# BMS_Design_3_New_Part_Monitor.net
KiCad netlist of a schematic drawn in Altium Designer
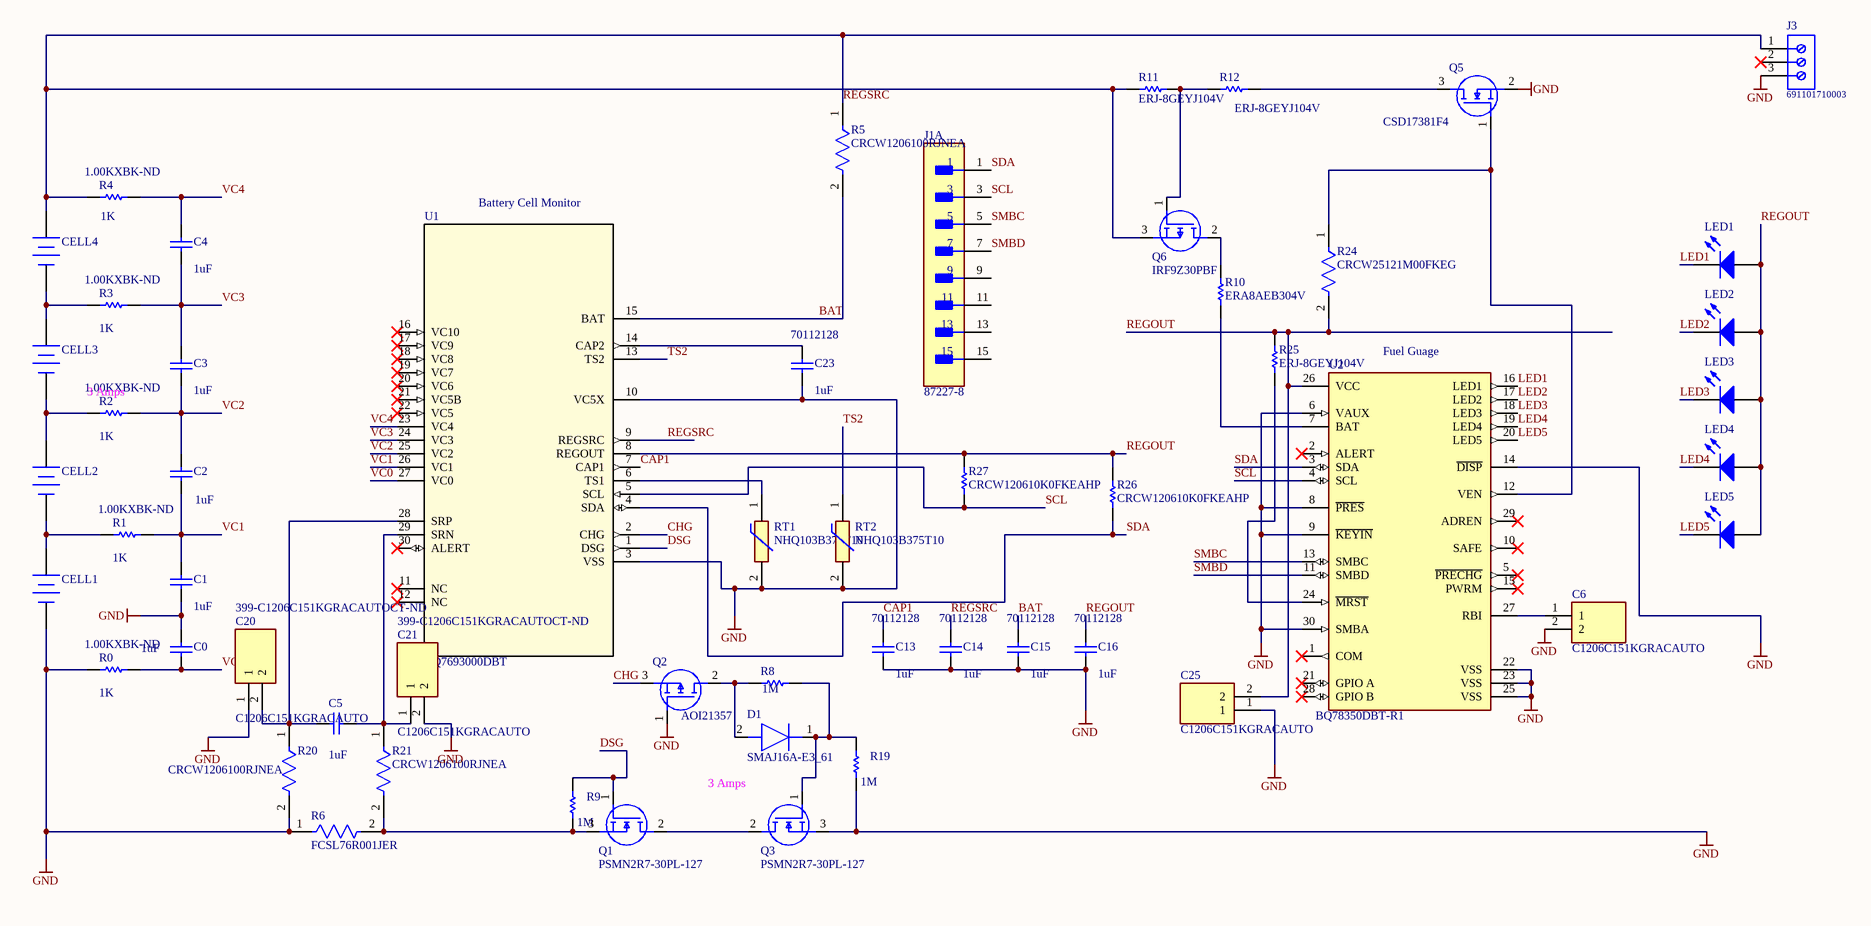
[diagram p0: BMS Design 3 New Part Monitor.SchDoc]

(export (version "E")
  (design (tool "Eeschema 10.0.6"))
  (components
    (comp (ref "C0")
      (value "1uF")
      (footprint "RAD-0.3")
      (description "Capacitor")
      (fields (field (name "PUBLISHER") "Altium Limited"))
      (libsource (lib "Miscellaneous Devices") (part "Cap"))
    )
    (comp (ref "C1")
      (value "1uF")
      (footprint "RAD-0.3")
      (description "Capacitor")
      (fields (field (name "PUBLISHER") "Altium Limited"))
      (libsource (lib "Miscellaneous Devices") (part "Cap"))
    )
    (comp (ref "C2")
      (value "1uF")
      (footprint "RAD-0.3")
      (description "Capacitor")
      (fields (field (name "PUBLISHER") "Altium Limited"))
      (libsource (lib "Miscellaneous Devices") (part "Cap"))
    )
    (comp (ref "C3")
      (value "1uF")
      (footprint "RAD-0.3")
      (description "Capacitor")
      (fields (field (name "PUBLISHER") "Altium Limited"))
      (libsource (lib "Miscellaneous Devices") (part "Cap"))
    )
    (comp (ref "C4")
      (value "1uF")
      (footprint "RAD-0.3")
      (description "Capacitor")
      (fields (field (name "PUBLISHER") "Altium Limited"))
      (libsource (lib "Miscellaneous Devices") (part "Cap"))
    )
    (comp (ref "C5")
      (value "1uF")
      (footprint "RAD-0.3")
      (description "Capacitor")
      (fields (field (name "PUBLISHER") "Altium Limited"))
      (libsource (lib "Miscellaneous Devices") (part "Cap"))
    )
    (comp (ref "C6")
      (value "C1206C151KGRACAUTO")
      (footprint "SamacSys:CAPC3216X180N")
      (description "Capacitor Network")
      (libsource (lib "*") (part "C1206C151KGRACAUTO"))
    )
    (comp (ref "C13")
      (value "1uF")
      (footprint "RAD-0.3")
      (description "Capacitor")
      (fields (field (name "SUPPLIER PART NUMBER 1") "70112128") (field (name "PUBLISHER") "Altium Limited"))
      (libsource (lib "Miscellaneous Devices") (part "Cap"))
    )
    (comp (ref "C14")
      (value "1uF")
      (footprint "RAD-0.3")
      (description "Capacitor")
      (fields (field (name "SUPPLIER PART NUMBER 1") "70112128") (field (name "PUBLISHER") "Altium Limited"))
      (libsource (lib "Miscellaneous Devices") (part "Cap"))
    )
    (comp (ref "C15")
      (value "1uF")
      (footprint "RAD-0.3")
      (description "Capacitor")
      (fields (field (name "SUPPLIER PART NUMBER 1") "70112128") (field (name "PUBLISHER") "Altium Limited"))
      (libsource (lib "Miscellaneous Devices") (part "Cap"))
    )
    (comp (ref "C16")
      (value "1uF")
      (footprint "RAD-0.3")
      (description "Capacitor")
      (fields (field (name "SUPPLIER PART NUMBER 1") "70112128") (field (name "PUBLISHER") "Altium Limited"))
      (libsource (lib "Miscellaneous Devices") (part "Cap"))
    )
    (comp (ref "C20")
      (value "C1206C151KGRACAUTO")
      (footprint "SamacSys:CAPC3216X180N")
      (description "Capacitor Network")
      (fields (field (name "SUPPLIER PART NUMBER 1") "399-C1206C151KGRACAUTOCT-ND"))
      (libsource (lib "") (part "C1206C151KGRACAUTO_1"))
    )
    (comp (ref "C21")
      (value "C1206C151KGRACAUTO")
      (footprint "SamacSys:CAPC3216X180N")
      (description "Capacitor Network")
      (fields (field (name "SUPPLIER PART NUMBER 1") "399-C1206C151KGRACAUTOCT-ND"))
      (libsource (lib "") (part "C1206C151KGRACAUTO_1"))
    )
    (comp (ref "C23")
      (value "1uF")
      (footprint "RAD-0.3")
      (description "Capacitor")
      (fields (field (name "SUPPLIER PART NUMBER 1") "70112128") (field (name "PUBLISHER") "Altium Limited"))
      (libsource (lib "Miscellaneous Devices") (part "Cap"))
    )
    (comp (ref "C25")
      (value "C1206C151KGRACAUTO")
      (footprint "SamacSys:CAPC3216X180N")
      (description "Capacitor Network")
      (libsource (lib "") (part "C1206C151KGRACAUTO_2"))
    )
    (comp (ref "CELL1")
      (value "~")
      (footprint "BAT-2")
      (description "Multicell Battery")
      (fields (field (name "PUBLISHER") "Altium Limited"))
      (libsource (lib "Miscellaneous Devices") (part "Battery"))
    )
    (comp (ref "CELL2")
      (value "~")
      (footprint "BAT-2")
      (description "Multicell Battery")
      (fields (field (name "PUBLISHER") "Altium Limited"))
      (libsource (lib "Miscellaneous Devices") (part "Battery"))
    )
    (comp (ref "CELL3")
      (value "~")
      (footprint "BAT-2")
      (description "Multicell Battery")
      (fields (field (name "PUBLISHER") "Altium Limited"))
      (libsource (lib "Miscellaneous Devices") (part "Battery"))
    )
    (comp (ref "CELL4")
      (value "~")
      (footprint "BAT-2")
      (description "Multicell Battery")
      (fields (field (name "PUBLISHER") "Altium Limited"))
      (libsource (lib "Miscellaneous Devices") (part "Battery"))
    )
    (comp (ref "D1")
      (value "SMAJ16A-E3_61")
      (footprint "SamacSys:DIOM5127X229N")
      (description "Diode")
      (fields
        (field (name "MANUFACTURER_PART_NUMBER") "SMAJ16A-E3/61")
        (field (name "MOUSER PART NUMBER") "625-SMAJ16A-E3")
      )
      (libsource (lib "*") (part "SMAJ16A-E3_61"))
    )
    (comp (ref "J1")
      (value "87227-8")
      (footprint "FP-87227-8-MFG")
      (description "CONN HEADER VERT 16POS 2.54MM")
      (fields
        (field (name "MANUFACTURER") "TE Connectivity")
        (field (name "OCTOPART") "https://octopart.com/87227-8-te+connectivity-39407754")
      )
      (libsource (lib "Altium Content Vault") (part "4b6d22b45e2f925f038cba5d936fbcc"))
    )
    (comp (ref "J3")
      (value "691101710003")
      (footprint "691101710003")
      (description "Series 101 - 5.00 mm Horizontal Entry Modular with Pressure Clamp WR-TBL, 3 pin")
      (fields (field (name "MANUFACTURER") "Wurth Elektronik") (field (name "PUBLISHER") "WurthElektronik"))
      (libsource (lib "Altium Content Vault") (part "WE-CN-1P-F-TB3"))
    )
    (comp (ref "LED1")
      (value "~")
      (footprint "LED-0")
      (description "Typical INFRARED GaAs LED")
      (fields (field (name "PUBLISHER") "Altium Limited"))
      (libsource (lib "Miscellaneous Devices") (part "LED0"))
    )
    (comp (ref "LED2")
      (value "~")
      (footprint "LED-0")
      (description "Typical INFRARED GaAs LED")
      (fields (field (name "PUBLISHER") "Altium Limited"))
      (libsource (lib "Miscellaneous Devices") (part "LED0"))
    )
    (comp (ref "LED3")
      (value "~")
      (footprint "LED-0")
      (description "Typical INFRARED GaAs LED")
      (fields (field (name "PUBLISHER") "Altium Limited"))
      (libsource (lib "Miscellaneous Devices") (part "LED0"))
    )
    (comp (ref "LED4")
      (value "~")
      (footprint "LED-0")
      (description "Typical INFRARED GaAs LED")
      (fields (field (name "PUBLISHER") "Altium Limited"))
      (libsource (lib "Miscellaneous Devices") (part "LED0"))
    )
    (comp (ref "LED5")
      (value "~")
      (footprint "LED-0")
      (description "Typical INFRARED GaAs LED")
      (fields (field (name "PUBLISHER") "Altium Limited"))
      (libsource (lib "Miscellaneous Devices") (part "LED0"))
    )
    (comp (ref "Q1")
      (value "PSMN2R7-30PL-127")
      (footprint "TO-220AB")
      (description "MOSFET (N-Channel)")
      (fields
        (field (name "MANUFACTURER_PART_NUMBER") "PSMN2R7-30PL,127")
        (field (name "MOUSER PART NUMBER") "771-PSMN2R730PL127")
      )
      (libsource (lib "*") (part "PSMN2R7-30PL,127"))
    )
    (comp (ref "Q2")
      (value "AOI21357")
      (footprint "SamacSys:TO229P239X654X854-3P")
      (description "MOSFET (P-Channel)")
      (libsource (lib "*") (part "AOI21357"))
    )
    (comp (ref "Q3")
      (value "PSMN2R7-30PL-127")
      (footprint "TO-220AB")
      (description "MOSFET (N-Channel)")
      (fields
        (field (name "MANUFACTURER_PART_NUMBER") "PSMN2R7-30PL,127")
        (field (name "MOUSER PART NUMBER") "771-PSMN2R730PL127")
      )
      (libsource (lib "*") (part "PSMN2R7-30PL,127"))
    )
    (comp (ref "Q5")
      (value "CSD17381F4")
      (footprint "SamacSys:CSD17381F4")
      (description "MOSFET (N-Channel)")
      (libsource (lib "*") (part "CSD17381F4"))
    )
    (comp (ref "Q6")
      (value "IRF9Z30PBF")
      (footprint "SamacSys:TO254P465X1024X2050-3P")
      (description "MOSFET (P-Channel)")
      (fields (field (name "MOUSER PART NUMBER") "844-IRF9Z30PBF"))
      (libsource (lib "*") (part "IRF9Z30PBF"))
    )
    (comp (ref "R0")
      (value "1K")
      (footprint "AXIAL-0.3")
      (description "Resistor")
      (fields
        (field (name "SUPPLIER PART NUMBER 1") "1.00KXBK-ND")
        (field (name "PUBLISHER") "Altium Limited")
      )
      (libsource (lib "Miscellaneous Devices") (part "Res1"))
    )
    (comp (ref "R1")
      (value "1K")
      (footprint "AXIAL-0.3")
      (description "Resistor")
      (fields
        (field (name "SUPPLIER PART NUMBER 1") "1.00KXBK-ND")
        (field (name "PUBLISHER") "Altium Limited")
      )
      (libsource (lib "Miscellaneous Devices") (part "Res1"))
    )
    (comp (ref "R2")
      (value "1K")
      (footprint "AXIAL-0.3")
      (description "Resistor")
      (fields
        (field (name "SUPPLIER PART NUMBER 1") "1.00KXBK-ND")
        (field (name "PUBLISHER") "Altium Limited")
      )
      (libsource (lib "Miscellaneous Devices") (part "Res1"))
    )
    (comp (ref "R3")
      (value "1K")
      (footprint "AXIAL-0.3")
      (description "Resistor")
      (fields
        (field (name "SUPPLIER PART NUMBER 1") "1.00KXBK-ND")
        (field (name "PUBLISHER") "Altium Limited")
      )
      (libsource (lib "Miscellaneous Devices") (part "Res1"))
    )
    (comp (ref "R4")
      (value "1K")
      (footprint "AXIAL-0.3")
      (description "Resistor")
      (fields
        (field (name "SUPPLIER PART NUMBER 1") "1.00KXBK-ND")
        (field (name "PUBLISHER") "Altium Limited")
      )
      (libsource (lib "Miscellaneous Devices") (part "Res1"))
    )
    (comp (ref "R5")
      (value "CRCW1206100RJNEA")
      (footprint "FP-CRCW1206-e3-IPC_B")
      (description "RES Thick Film, 100Ω, 5%, 0.25W, 200ppm/°C, 1206")
      (fields (field (name "TOLERANCE") "5%"))
      (libsource (lib "Altium Content Vault") (part "1029c3af85768c4190bb7ad29bc67b5"))
    )
    (comp (ref "R6")
      (value "FCSL76R001JER")
      (footprint "FP-FCSL76-0R001-MFG")
      (description "RES 0.001 OHM 3W 3015 WIDE")
      (fields (field (name "TOLERANCE") "5%"))
      (libsource (lib "Altium Content Vault") (part "1029c3af85768c4190bb7ad29bc67b5"))
    )
    (comp (ref "R8")
      (value "1M")
      (footprint "AXIAL-0.3")
      (description "Resistor")
      (fields (field (name "PUBLISHER") "Altium Limited"))
      (libsource (lib "Miscellaneous Devices") (part "Res1"))
    )
    (comp (ref "R9")
      (value "1M")
      (footprint "AXIAL-0.3")
      (description "Resistor")
      (fields (field (name "PUBLISHER") "Altium Limited"))
      (libsource (lib "Miscellaneous Devices") (part "Res1"))
    )
    (comp (ref "R10")
      (value "ERA8AEB304V")
      (footprint "RESC3216X70X50LL20T25")
      (fields (field (name "MANUFACTURER") "Panasonic"))
      (libsource (lib "Altium Content Vault") (part "RES"))
    )
    (comp (ref "R11")
      (value "ERJ-8GEYJ104V")
      (footprint "RESC3216X70X50LL05T20")
      (fields (field (name "MANUFACTURER") "Panasonic"))
      (libsource (lib "Altium Content Vault") (part "RES"))
    )
    (comp (ref "R12")
      (value "ERJ-8GEYJ104V")
      (footprint "RESC3216X70X50LL05T20")
      (fields (field (name "MANUFACTURER") "Panasonic"))
      (libsource (lib "Altium Content Vault") (part "RES"))
    )
    (comp (ref "R19")
      (value "1M")
      (footprint "AXIAL-0.3")
      (description "Resistor")
      (fields (field (name "PUBLISHER") "Altium Limited"))
      (libsource (lib "Miscellaneous Devices") (part "Res1"))
    )
    (comp (ref "R20")
      (value "CRCW1206100RJNEA")
      (footprint "FP-CRCW1206-e3-IPC_B")
      (description "RES Thick Film, 100Ω, 5%, 0.25W, 200ppm/°C, 1206")
      (fields (field (name "TOLERANCE") "5%"))
      (libsource (lib "Altium Content Vault") (part "1029c3af85768c4190bb7ad29bc67b5"))
    )
    (comp (ref "R21")
      (value "CRCW1206100RJNEA")
      (footprint "FP-CRCW1206-e3-IPC_B")
      (description "RES Thick Film, 100Ω, 5%, 0.25W, 200ppm/°C, 1206")
      (fields (field (name "TOLERANCE") "5%"))
      (libsource (lib "Altium Content Vault") (part "1029c3af85768c4190bb7ad29bc67b5"))
    )
    (comp (ref "R24")
      (value "CRCW25121M00FKEG")
      (footprint "FP-CRCW2512-e3-IPC_C")
      (description "RES Thick Film, 1MΩ, 1%, 1W, 100ppm/°C, 2512")
      (fields (field (name "TOLERANCE") "1%"))
      (libsource (lib "Altium Content Vault") (part "1029c3af85768c4190bb7ad29bc67b5"))
    )
    (comp (ref "R25")
      (value "ERJ-8GEYJ104V")
      (footprint "RESC3216X70X50LL05T20")
      (fields (field (name "MANUFACTURER") "Panasonic"))
      (libsource (lib "Altium Content Vault") (part "RES"))
    )
    (comp (ref "R26")
      (value "CRCW120610K0FKEAHP")
      (footprint "RESC3116X65X50NL20T20")
      (fields (field (name "MANUFACTURER") "Vishay Dale"))
      (libsource (lib "Altium Content Vault") (part "RES"))
    )
    (comp (ref "R27")
      (value "CRCW120610K0FKEAHP")
      (footprint "RESC3116X65X50NL20T20")
      (fields (field (name "MANUFACTURER") "Vishay Dale"))
      (libsource (lib "Altium Content Vault") (part "RES"))
    )
    (comp (ref "RT1")
      (value "NHQ103B375T10")
      (footprint "SamacSys:RESC2113X66N")
      (description "Thermistor")
      (libsource (lib "*") (part "NHQ103B375T10"))
    )
    (comp (ref "RT2")
      (value "NHQ103B375T10")
      (footprint "SamacSys:RESC2113X66N")
      (description "Thermistor")
      (libsource (lib "*") (part "NHQ103B375T10"))
    )
    (comp (ref "U1")
      (value "BQ7693000DBT")
      (footprint "BQ7693000DBT:DBT0030A_N")
      (description "No Description Available")
      (fields (field (name "COPYRIGHT") "Copyright (C) 2022 Ultra Librarian. All rights reserved."))
      (libsource (lib "BQ7693000DBT") (part "BQ7693000DBT"))
    )
    (comp (ref "U2")
      (value "BQ78350DBT-R1")
      (footprint "FP-DBT0030A-IPC_C")
      (description "IC BATTERY MGMT CTRLR 30TSSOP")
      (libsource (lib "Altium Content Vault") (part "ce2f43281ae33b5194046e95201acc2"))
    )
  )
  (nets
    (net (code "1") (name "/BAT") (class "Default")
      (node (ref "C15") (pin "2") (pinfunction "2_2") (pintype "passive"))
      (node (ref "R5") (pin "2") (pinfunction "2_2") (pintype "passive"))
      (node (ref "U1") (pin "15") (pinfunction "BAT_15") (pintype "power_in"))
    )
    (net (code "2") (name "/CAP1") (class "Default")
      (node (ref "C13") (pin "2") (pinfunction "2_2") (pintype "passive"))
      (node (ref "U1") (pin "7") (pinfunction "CAP1_7") (pintype "output"))
    )
    (net (code "3") (name "/CHG") (class "Default")
      (node (ref "Q2") (pin "3") (pinfunction "S_3") (pintype "passive"))
      (node (ref "U1") (pin "2") (pinfunction "CHG_2") (pintype "output"))
    )
    (net (code "4") (name "/DSG") (class "Default")
      (node (ref "Q1") (pin "1") (pinfunction "G_1") (pintype "passive"))
      (node (ref "R9") (pin "2") (pinfunction "2_2") (pintype "passive"))
      (node (ref "U1") (pin "1") (pinfunction "DSG_1") (pintype "output"))
    )
    (net (code "5") (name "/LED1") (class "Default")
      (node (ref "LED1") (pin "2") (pinfunction "K_2") (pintype "passive"))
      (node (ref "U2") (pin "16") (pinfunction "LED1_16") (pintype "output"))
    )
    (net (code "6") (name "/LED2") (class "Default")
      (node (ref "LED2") (pin "2") (pinfunction "K_2") (pintype "passive"))
      (node (ref "U2") (pin "17") (pinfunction "LED2_17") (pintype "output"))
    )
    (net (code "7") (name "/LED3") (class "Default")
      (node (ref "LED3") (pin "2") (pinfunction "K_2") (pintype "passive"))
      (node (ref "U2") (pin "18") (pinfunction "LED3_18") (pintype "output"))
    )
    (net (code "8") (name "/LED4") (class "Default")
      (node (ref "LED4") (pin "2") (pinfunction "K_2") (pintype "passive"))
      (node (ref "U2") (pin "19") (pinfunction "LED4_19") (pintype "output"))
    )
    (net (code "9") (name "/LED5") (class "Default")
      (node (ref "LED5") (pin "2") (pinfunction "K_2") (pintype "passive"))
      (node (ref "U2") (pin "20") (pinfunction "LED5_20") (pintype "output"))
    )
    (net (code "10") (name "/REGOUT") (class "Default")
      (node (ref "C16") (pin "2") (pinfunction "2_2") (pintype "passive"))
      (node (ref "C25") (pin "2") (pinfunction "2_2") (pintype "passive"))
      (node (ref "LED1") (pin "1") (pinfunction "A_1") (pintype "passive"))
      (node (ref "LED2") (pin "1") (pinfunction "A_1") (pintype "passive"))
      (node (ref "LED3") (pin "1") (pinfunction "A_1") (pintype "passive"))
      (node (ref "LED4") (pin "1") (pinfunction "A_1") (pintype "passive"))
      (node (ref "LED5") (pin "1") (pinfunction "A_1") (pintype "passive"))
      (node (ref "R24") (pin "2") (pinfunction "2_2") (pintype "passive"))
      (node (ref "R25") (pin "2") (pinfunction "2_2") (pintype "passive"))
      (node (ref "R26") (pin "2") (pinfunction "2_2") (pintype "passive"))
      (node (ref "R27") (pin "2") (pinfunction "2_2") (pintype "passive"))
      (node (ref "U1") (pin "8") (pinfunction "REGOUT_8") (pintype "power_in"))
      (node (ref "U2") (pin "26") (pinfunction "VCC_26") (pintype "power_in"))
    )
    (net (code "11") (name "/REGSRC") (class "Default")
      (node (ref "C14") (pin "2") (pinfunction "2_2") (pintype "passive"))
      (node (ref "CELL4") (pin "1") (pinfunction "+_1") (pintype "passive"))
      (node (ref "J3") (pin "1") (pinfunction "1_1") (pintype "passive"))
      (node (ref "Q6") (pin "3") (pinfunction "S_3") (pintype "passive"))
      (node (ref "R11") (pin "1") (pinfunction "1_1") (pintype "passive"))
      (node (ref "R4") (pin "1") (pinfunction "1_1") (pintype "passive"))
      (node (ref "R5") (pin "1") (pinfunction "1_1") (pintype "passive"))
      (node (ref "U1") (pin "9") (pinfunction "REGSRC_9") (pintype "output"))
    )
    (net (code "12") (name "/SCL") (class "Default")
      (node (ref "J1") (pin "3") (pinfunction "3_3") (pintype "passive"))
      (node (ref "R27") (pin "1") (pinfunction "1_1") (pintype "passive"))
      (node (ref "U1") (pin "5") (pinfunction "SCL_5") (pintype "input"))
      (node (ref "U2") (pin "4") (pinfunction "SCL_4") (pintype "bidirectional"))
    )
    (net (code "13") (name "/SDA") (class "Default")
      (node (ref "J1") (pin "1") (pinfunction "1_1") (pintype "passive"))
      (node (ref "R26") (pin "1") (pinfunction "1_1") (pintype "passive"))
      (node (ref "U1") (pin "4") (pinfunction "SDA_4") (pintype "bidirectional"))
      (node (ref "U2") (pin "3") (pinfunction "SDA_3") (pintype "bidirectional"))
    )
    (net (code "14") (name "/SMBC") (class "Default")
      (node (ref "J1") (pin "5") (pinfunction "5_5") (pintype "passive"))
      (node (ref "U2") (pin "13") (pinfunction "SMBC_13") (pintype "bidirectional"))
    )
    (net (code "15") (name "/SMBD") (class "Default")
      (node (ref "J1") (pin "7") (pinfunction "7_7") (pintype "passive"))
      (node (ref "U2") (pin "11") (pinfunction "SMBD_11") (pintype "bidirectional"))
    )
    (net (code "16") (name "/TS2") (class "Default")
      (node (ref "RT2") (pin "1") (pinfunction "1_1") (pintype "passive"))
      (node (ref "U1") (pin "13") (pinfunction "TS2_13") (pintype "passive"))
    )
    (net (code "17") (name "/VC0") (class "Default")
      (node (ref "C0") (pin "1") (pinfunction "1_1") (pintype "passive"))
      (node (ref "R0") (pin "2") (pinfunction "2_2") (pintype "passive"))
      (node (ref "U1") (pin "27") (pinfunction "VC0_27") (pintype "passive"))
    )
    (net (code "18") (name "/VC1") (class "Default")
      (node (ref "C1") (pin "2") (pinfunction "2_2") (pintype "passive"))
      (node (ref "C2") (pin "1") (pinfunction "1_1") (pintype "passive"))
      (node (ref "R1") (pin "2") (pinfunction "2_2") (pintype "passive"))
      (node (ref "U1") (pin "26") (pinfunction "VC1_26") (pintype "passive"))
    )
    (net (code "19") (name "/VC2") (class "Default")
      (node (ref "C2") (pin "2") (pinfunction "2_2") (pintype "passive"))
      (node (ref "C3") (pin "1") (pinfunction "1_1") (pintype "passive"))
      (node (ref "R2") (pin "2") (pinfunction "2_2") (pintype "passive"))
      (node (ref "U1") (pin "25") (pinfunction "VC2_25") (pintype "passive"))
    )
    (net (code "20") (name "/VC3") (class "Default")
      (node (ref "C3") (pin "2") (pinfunction "2_2") (pintype "passive"))
      (node (ref "C4") (pin "1") (pinfunction "1_1") (pintype "passive"))
      (node (ref "R3") (pin "2") (pinfunction "2_2") (pintype "passive"))
      (node (ref "U1") (pin "24") (pinfunction "VC3_24") (pintype "passive"))
    )
    (net (code "21") (name "/VC4") (class "Default")
      (node (ref "C4") (pin "2") (pinfunction "2_2") (pintype "passive"))
      (node (ref "R4") (pin "2") (pinfunction "2_2") (pintype "passive"))
      (node (ref "U1") (pin "23") (pinfunction "VC4_23") (pintype "passive"))
    )
    (net (code "22") (name "GND") (class "Default")
      (node (ref "C0") (pin "2") (pinfunction "2_2") (pintype "passive"))
      (node (ref "C1") (pin "1") (pinfunction "1_1") (pintype "passive"))
      (node (ref "C13") (pin "1") (pinfunction "1_1") (pintype "passive"))
      (node (ref "C14") (pin "1") (pinfunction "1_1") (pintype "passive"))
      (node (ref "C15") (pin "1") (pinfunction "1_1") (pintype "passive"))
      (node (ref "C16") (pin "1") (pinfunction "1_1") (pintype "passive"))
      (node (ref "C20") (pin "1") (pinfunction "1_1") (pintype "passive"))
      (node (ref "C21") (pin "2") (pinfunction "2_2") (pintype "passive"))
      (node (ref "C23") (pin "1") (pinfunction "1_1") (pintype "passive"))
      (node (ref "C25") (pin "1") (pinfunction "1_1") (pintype "passive"))
      (node (ref "C6") (pin "2") (pinfunction "2_2") (pintype "passive"))
      (node (ref "CELL1") (pin "2") (pinfunction "-_2") (pintype "passive"))
      (node (ref "J3") (pin "3") (pinfunction "3_3") (pintype "passive"))
      (node (ref "Q2") (pin "1") (pinfunction "G_1") (pintype "passive"))
      (node (ref "Q3") (pin "3") (pinfunction "S_3") (pintype "passive"))
      (node (ref "Q5") (pin "2") (pinfunction "S_2") (pintype "passive"))
      (node (ref "R0") (pin "1") (pinfunction "1_1") (pintype "passive"))
      (node (ref "R19") (pin "1") (pinfunction "1_1") (pintype "passive"))
      (node (ref "R20") (pin "2") (pinfunction "2_2") (pintype "passive"))
      (node (ref "R6") (pin "1") (pinfunction "1_1") (pintype "passive"))
      (node (ref "RT1") (pin "2") (pinfunction "2_2") (pintype "passive"))
      (node (ref "RT2") (pin "2") (pinfunction "2_2") (pintype "passive"))
      (node (ref "U1") (pin "10") (pinfunction "VC5X_10") (pintype "passive"))
      (node (ref "U1") (pin "3") (pinfunction "VSS_3") (pintype "power_in"))
      (node (ref "U2") (pin "14") (pinfunction "~{DISP}_14") (pintype "passive"))
      (node (ref "U2") (pin "22") (pinfunction "VSS_22") (pintype "passive"))
      (node (ref "U2") (pin "23") (pinfunction "VSS_23") (pintype "power_in"))
      (node (ref "U2") (pin "25") (pinfunction "VSS_25") (pintype "power_in"))
      (node (ref "U2") (pin "30") (pinfunction "SMBA_30") (pintype "input"))
      (node (ref "U2") (pin "6") (pinfunction "VAUX_6") (pintype "input"))
      (node (ref "U2") (pin "8") (pinfunction "~{PRES}_8") (pintype "passive"))
      (node (ref "U2") (pin "9") (pinfunction "~{KEYIN}_9") (pintype "passive"))
    )
    (net (code "23") (name "Net-(CELL1-+)") (class "Default")
      (node (ref "CELL1") (pin "1") (pinfunction "+_1") (pintype "passive"))
      (node (ref "CELL2") (pin "2") (pinfunction "-_2") (pintype "passive"))
      (node (ref "R1") (pin "1") (pinfunction "1_1") (pintype "passive"))
    )
    (net (code "24") (name "Net-(CELL2-+)") (class "Default")
      (node (ref "CELL2") (pin "1") (pinfunction "+_1") (pintype "passive"))
      (node (ref "CELL3") (pin "2") (pinfunction "-_2") (pintype "passive"))
      (node (ref "R2") (pin "1") (pinfunction "1_1") (pintype "passive"))
    )
    (net (code "25") (name "Net-(CELL3-+)") (class "Default")
      (node (ref "CELL3") (pin "1") (pinfunction "+_1") (pintype "passive"))
      (node (ref "CELL4") (pin "2") (pinfunction "-_2") (pintype "passive"))
      (node (ref "R3") (pin "1") (pinfunction "1_1") (pintype "passive"))
    )
    (net (code "26") (name "Net-(D1-A)") (class "Default")
      (node (ref "D1") (pin "2") (pinfunction "A_2") (pintype "passive"))
      (node (ref "Q2") (pin "2") (pinfunction "D_2") (pintype "passive"))
      (node (ref "R8") (pin "2") (pinfunction "2_2") (pintype "passive"))
    )
    (net (code "27") (name "Net-(D1-K)") (class "Default")
      (node (ref "D1") (pin "1") (pinfunction "K_1") (pintype "passive"))
      (node (ref "Q3") (pin "1") (pinfunction "G_1") (pintype "passive"))
      (node (ref "R19") (pin "2") (pinfunction "2_2") (pintype "passive"))
      (node (ref "R8") (pin "1") (pinfunction "1_1") (pintype "passive"))
    )
    (net (code "28") (name "Net-(Q1-D)") (class "Default")
      (node (ref "Q1") (pin "2") (pinfunction "D_2") (pintype "passive"))
      (node (ref "Q3") (pin "2") (pinfunction "D_2") (pintype "passive"))
    )
    (net (code "29") (name "Net-(Q1-S)") (class "Default")
      (node (ref "Q1") (pin "3") (pinfunction "S_3") (pintype "passive"))
      (node (ref "R21") (pin "2") (pinfunction "2_2") (pintype "passive"))
      (node (ref "R6") (pin "2") (pinfunction "2_2") (pintype "passive"))
      (node (ref "R9") (pin "1") (pinfunction "1_1") (pintype "passive"))
    )
    (net (code "30") (name "Net-(Q5-D)") (class "Default")
      (node (ref "Q5") (pin "3") (pinfunction "D_3") (pintype "passive"))
      (node (ref "R12") (pin "2") (pinfunction "2_2") (pintype "passive"))
    )
    (net (code "31") (name "Net-(Q5-G)") (class "Default")
      (node (ref "Q5") (pin "1") (pinfunction "G_1") (pintype "passive"))
      (node (ref "R24") (pin "1") (pinfunction "1_1") (pintype "passive"))
      (node (ref "U2") (pin "12") (pinfunction "VEN_12") (pintype "output"))
    )
    (net (code "32") (name "Net-(Q6-D)") (class "Default")
      (node (ref "Q6") (pin "2") (pinfunction "D_2") (pintype "passive"))
      (node (ref "R10") (pin "2") (pinfunction "2_2") (pintype "passive"))
    )
    (net (code "33") (name "Net-(Q6-G)") (class "Default")
      (node (ref "Q6") (pin "1") (pinfunction "G_1") (pintype "passive"))
      (node (ref "R11") (pin "2") (pinfunction "2_2") (pintype "passive"))
      (node (ref "R12") (pin "1") (pinfunction "1_1") (pintype "passive"))
    )
    (net (code "34") (name "Net-(U1-CAP2)") (class "Default")
      (node (ref "C23") (pin "2") (pinfunction "2_2") (pintype "passive"))
      (node (ref "U1") (pin "14") (pinfunction "CAP2_14") (pintype "output"))
    )
    (net (code "35") (name "Net-(U1-SRN)") (class "Default")
      (node (ref "C21") (pin "1") (pinfunction "1_1") (pintype "passive"))
      (node (ref "C5") (pin "2") (pinfunction "2_2") (pintype "passive"))
      (node (ref "R21") (pin "1") (pinfunction "1_1") (pintype "passive"))
      (node (ref "U1") (pin "29") (pinfunction "SRN_29") (pintype "passive"))
    )
    (net (code "36") (name "Net-(U1-SRP)") (class "Default")
      (node (ref "C20") (pin "2") (pinfunction "2_2") (pintype "passive"))
      (node (ref "C5") (pin "1") (pinfunction "1_1") (pintype "passive"))
      (node (ref "R20") (pin "1") (pinfunction "1_1") (pintype "passive"))
      (node (ref "U1") (pin "28") (pinfunction "SRP_28") (pintype "passive"))
    )
    (net (code "37") (name "Net-(U1-TS1)") (class "Default")
      (node (ref "RT1") (pin "1") (pinfunction "1_1") (pintype "passive"))
      (node (ref "U1") (pin "6") (pinfunction "TS1_6") (pintype "passive"))
    )
    (net (code "38") (name "Net-(U2-BAT)") (class "Default")
      (node (ref "R10") (pin "1") (pinfunction "1_1") (pintype "passive"))
      (node (ref "U2") (pin "7") (pinfunction "BAT_7") (pintype "passive"))
    )
    (net (code "39") (name "Net-(U2-RBI)") (class "Default")
      (node (ref "C6") (pin "1") (pinfunction "1_1") (pintype "passive"))
      (node (ref "U2") (pin "27") (pinfunction "RBI_27") (pintype "power_in"))
    )
    (net (code "40") (name "Net-(U2-~{MRST})") (class "Default")
      (node (ref "R25") (pin "1") (pinfunction "1_1") (pintype "passive"))
      (node (ref "U2") (pin "24") (pinfunction "~{MRST}_24") (pintype "input"))
    )
    (net (code "41") (name "unconnected-(J1-Pad9)") (class "Default")
      (node (ref "J1") (pin "9") (pinfunction "9_9") (pintype "passive"))
    )
    (net (code "42") (name "unconnected-(J1-Pad11)") (class "Default")
      (node (ref "J1") (pin "11") (pinfunction "11_11") (pintype "passive"))
    )
    (net (code "43") (name "unconnected-(J1-Pad13)") (class "Default")
      (node (ref "J1") (pin "13") (pinfunction "13_13") (pintype "passive"))
    )
    (net (code "44") (name "unconnected-(J1-Pad15)") (class "Default")
      (node (ref "J1") (pin "15") (pinfunction "15_15") (pintype "passive"))
    )
    (net (code "45") (name "unconnected-(J3-Pad2)") (class "Default")
      (node (ref "J3") (pin "2") (pinfunction "2_2") (pintype "passive+no_connect"))
    )
    (net (code "46") (name "unconnected-(U1-ALERT-Pad30)") (class "Default")
      (node (ref "U1") (pin "30") (pinfunction "ALERT_30") (pintype "bidirectional+no_connect"))
    )
    (net (code "47") (name "unconnected-(U1-NC-Pad11)") (class "Default")
      (node (ref "U1") (pin "11") (pinfunction "NC_11") (pintype "passive+no_connect"))
    )
    (net (code "48") (name "unconnected-(U1-NC-Pad12)") (class "Default")
      (node (ref "U1") (pin "12") (pinfunction "NC_12") (pintype "passive+no_connect"))
    )
    (net (code "49") (name "unconnected-(U1-VC5-Pad22)") (class "Default")
      (node (ref "U1") (pin "22") (pinfunction "VC5_22") (pintype "input+no_connect"))
    )
    (net (code "50") (name "unconnected-(U1-VC5B-Pad21)") (class "Default")
      (node (ref "U1") (pin "21") (pinfunction "VC5B_21") (pintype "input+no_connect"))
    )
    (net (code "51") (name "unconnected-(U1-VC6-Pad20)") (class "Default")
      (node (ref "U1") (pin "20") (pinfunction "VC6_20") (pintype "input+no_connect"))
    )
    (net (code "52") (name "unconnected-(U1-VC7-Pad19)") (class "Default")
      (node (ref "U1") (pin "19") (pinfunction "VC7_19") (pintype "input+no_connect"))
    )
    (net (code "53") (name "unconnected-(U1-VC8-Pad18)") (class "Default")
      (node (ref "U1") (pin "18") (pinfunction "VC8_18") (pintype "input+no_connect"))
    )
    (net (code "54") (name "unconnected-(U1-VC9-Pad17)") (class "Default")
      (node (ref "U1") (pin "17") (pinfunction "VC9_17") (pintype "input+no_connect"))
    )
    (net (code "55") (name "unconnected-(U1-VC10-Pad16)") (class "Default")
      (node (ref "U1") (pin "16") (pinfunction "VC10_16") (pintype "input+no_connect"))
    )
    (net (code "56") (name "unconnected-(U2-ADREN-Pad29)") (class "Default")
      (node (ref "U2") (pin "29") (pinfunction "ADREN_29") (pintype "output+no_connect"))
    )
    (net (code "57") (name "unconnected-(U2-ALERT-Pad2)") (class "Default")
      (node (ref "U2") (pin "2") (pinfunction "ALERT_2") (pintype "input+no_connect"))
    )
    (net (code "58") (name "unconnected-(U2-COM-Pad1)") (class "Default")
      (node (ref "U2") (pin "1") (pinfunction "COM_1") (pintype "output+no_connect"))
    )
    (net (code "59") (name "unconnected-(U2-GPIO_A-Pad21)") (class "Default")
      (node (ref "U2") (pin "21") (pinfunction "GPIO_A_21") (pintype "bidirectional+no_connect"))
    )
    (net (code "60") (name "unconnected-(U2-GPIO_B-Pad28)") (class "Default")
      (node (ref "U2") (pin "28") (pinfunction "GPIO_B_28") (pintype "bidirectional+no_connect"))
    )
    (net (code "61") (name "unconnected-(U2-PWRM-Pad15)") (class "Default")
      (node (ref "U2") (pin "15") (pinfunction "PWRM_15") (pintype "output+no_connect"))
    )
    (net (code "62") (name "unconnected-(U2-SAFE-Pad10)") (class "Default")
      (node (ref "U2") (pin "10") (pinfunction "SAFE_10") (pintype "output+no_connect"))
    )
    (net (code "63") (name "unconnected-(U2-~{PRECHG}-Pad5)") (class "Default")
      (node (ref "U2") (pin "5") (pinfunction "~{PRECHG}_5") (pintype "output+no_connect"))
    )
  )
)
